# reference_nrf52840_module.net
KiCad netlist of a schematic drawn in EAGLE
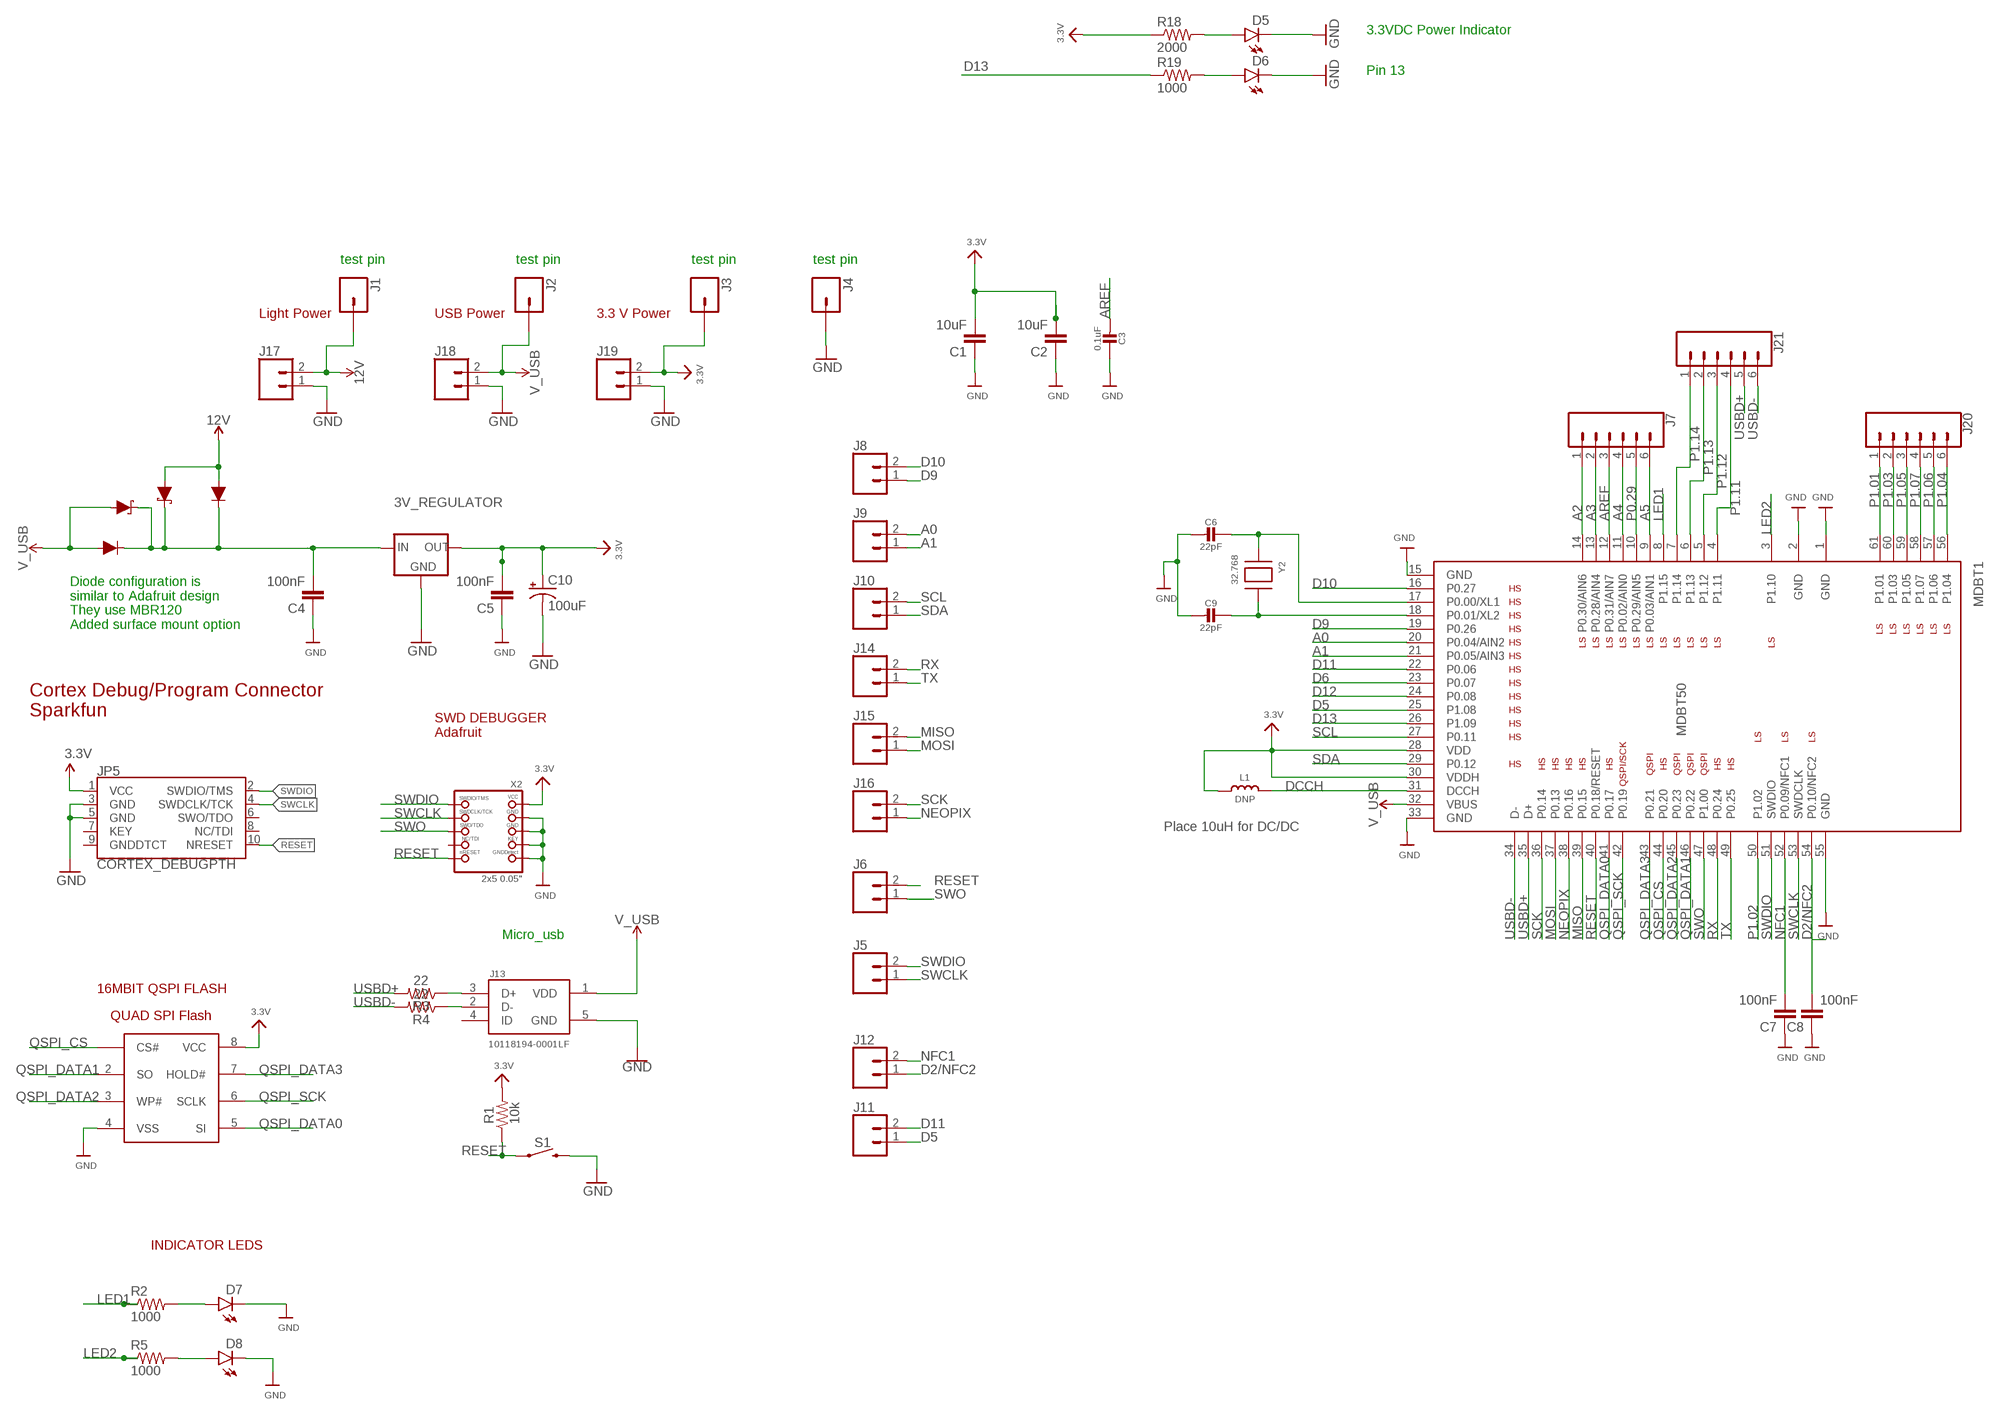
[diagram p0: schematic, sheet 1]

(export (version "E")
  (design (tool "Eeschema 10.0.6"))
  (components
    (comp (ref "3V_REGULATOR")
      (value "LDL1117_5V_REG")
      (footprint "eagle-import:SOT223")
      (libsource (lib "eagle-import") (part "LDL1117_5V_REG"))
    )
    (comp (ref "C1")
      (value "10uF")
      (footprint "eagle-import:0805")
      (libsource (lib "eagle-import") (part "10UF-0805-10V-10%"))
    )
    (comp (ref "C2")
      (value "10uF")
      (footprint "eagle-import:0805")
      (libsource (lib "eagle-import") (part "10UF-0805-10V-10%"))
    )
    (comp (ref "C3")
      (value "0.1uF")
      (footprint "eagle-import:_0805")
      (libsource (lib "eagle-import") (part "CAP_CERAMIC_0805"))
    )
    (comp (ref "C4")
      (value "100nF")
      (footprint "eagle-import:0805")
      (libsource (lib "eagle-import") (part "10UF-0805-10V-10%"))
    )
    (comp (ref "C5")
      (value "100nF")
      (footprint "eagle-import:0805")
      (libsource (lib "eagle-import") (part "10UF-0805-10V-10%"))
    )
    (comp (ref "C6")
      (value "22pF")
      (footprint "eagle-import:0603-NO")
      (libsource (lib "eagle-import") (part "CAP_CERAMIC0603_NO"))
    )
    (comp (ref "C7")
      (value "100nF")
      (footprint "eagle-import:0805")
      (libsource (lib "eagle-import") (part "10UF-0805-10V-10%"))
    )
    (comp (ref "C8")
      (value "100nF")
      (footprint "eagle-import:0805")
      (libsource (lib "eagle-import") (part "10UF-0805-10V-10%"))
    )
    (comp (ref "C9")
      (value "22pF")
      (footprint "eagle-import:0603-NO")
      (libsource (lib "eagle-import") (part "CAP_CERAMIC0603_NO"))
    )
    (comp (ref "C10")
      (value "100uF")
      (footprint "eagle-import:CPOL-RADIAL-2.5MM-6.5MM")
      (libsource (lib "eagle-import") (part "100UF-POLAR-RADIAL-2.5MM-25V-20%"))
    )
    (comp (ref "D1")
      (value "1A/50V/1.1V")
      (footprint "eagle-import:DIODE-1N4001")
      (libsource (lib "eagle-import") (part "DIODE-PTH"))
    )
    (comp (ref "D2")
      (value "1A/50V/1.1V")
      (footprint "eagle-import:DIODE-1N4001")
      (libsource (lib "eagle-import") (part "DIODE-PTH"))
    )
    (comp (ref "D3")
      (value "3A/40V/500mV")
      (footprint "eagle-import:SMA-DIODE")
      (libsource (lib "eagle-import") (part "DIODE-SCHOTTKY-B340A"))
    )
    (comp (ref "D4")
      (value "3A/40V/500mV")
      (footprint "eagle-import:SMA-DIODE")
      (libsource (lib "eagle-import") (part "DIODE-SCHOTTKY-B340A"))
    )
    (comp (ref "D5")
      (value "LED1206")
      (footprint "eagle-import:LED-1206")
      (libsource (lib "eagle-import") (part "LED1206"))
    )
    (comp (ref "D6")
      (value "LED1206")
      (footprint "eagle-import:LED-1206")
      (libsource (lib "eagle-import") (part "LED1206"))
    )
    (comp (ref "D7")
      (value "LED1206")
      (footprint "eagle-import:LED-1206")
      (libsource (lib "eagle-import") (part "LED1206"))
    )
    (comp (ref "D8")
      (value "LED1206")
      (footprint "eagle-import:LED-1206")
      (libsource (lib "eagle-import") (part "LED1206"))
    )
    (comp (ref "J1")
      (value "M01PTH")
      (footprint "eagle-import:1X01")
      (libsource (lib "eagle-import") (part "M01PTH"))
    )
    (comp (ref "J2")
      (value "M01PTH")
      (footprint "eagle-import:1X01")
      (libsource (lib "eagle-import") (part "M01PTH"))
    )
    (comp (ref "J3")
      (value "M01PTH")
      (footprint "eagle-import:1X01")
      (libsource (lib "eagle-import") (part "M01PTH"))
    )
    (comp (ref "J4")
      (value "M01PTH")
      (footprint "eagle-import:1X01")
      (libsource (lib "eagle-import") (part "M01PTH"))
    )
    (comp (ref "J5")
      (value "CONN_025MM")
      (footprint "eagle-import:SCREWTERMINAL-5MM-2")
      (libsource (lib "eagle-import") (part "CONN_025MM"))
    )
    (comp (ref "J6")
      (value "CONN_025MM")
      (footprint "eagle-import:SCREWTERMINAL-5MM-2")
      (libsource (lib "eagle-import") (part "CONN_025MM"))
    )
    (comp (ref "J7")
      (value "CONN_06NO_SILK_FEMALE_PTH")
      (footprint "eagle-import:1X06_NO_SILK")
      (libsource (lib "eagle-import") (part "CONN_06NO_SILK_FEMALE_PTH"))
    )
    (comp (ref "J8")
      (value "CONN_025MM")
      (footprint "eagle-import:SCREWTERMINAL-5MM-2")
      (libsource (lib "eagle-import") (part "CONN_025MM"))
    )
    (comp (ref "J9")
      (value "CONN_025MM")
      (footprint "eagle-import:SCREWTERMINAL-5MM-2")
      (libsource (lib "eagle-import") (part "CONN_025MM"))
    )
    (comp (ref "J10")
      (value "CONN_025MM")
      (footprint "eagle-import:SCREWTERMINAL-5MM-2")
      (libsource (lib "eagle-import") (part "CONN_025MM"))
    )
    (comp (ref "J11")
      (value "CONN_025MM")
      (footprint "eagle-import:SCREWTERMINAL-5MM-2")
      (libsource (lib "eagle-import") (part "CONN_025MM"))
    )
    (comp (ref "J12")
      (value "CONN_025MM")
      (footprint "eagle-import:SCREWTERMINAL-5MM-2")
      (libsource (lib "eagle-import") (part "CONN_025MM"))
    )
    (comp (ref "J13")
      (value "10118194-0001LF")
      (footprint "eagle-import:FRAMATOME_10118194-0001LF")
      (fields (field (name "MF") "Amphenol ICC"))
      (libsource (lib "eagle-import") (part "10118194-0001LF"))
    )
    (comp (ref "J14")
      (value "CONN_025MM")
      (footprint "eagle-import:SCREWTERMINAL-5MM-2")
      (libsource (lib "eagle-import") (part "CONN_025MM"))
    )
    (comp (ref "J15")
      (value "CONN_025MM")
      (footprint "eagle-import:SCREWTERMINAL-5MM-2")
      (libsource (lib "eagle-import") (part "CONN_025MM"))
    )
    (comp (ref "J16")
      (value "CONN_025MM")
      (footprint "eagle-import:SCREWTERMINAL-5MM-2")
      (libsource (lib "eagle-import") (part "CONN_025MM"))
    )
    (comp (ref "J17")
      (value "CONN_025MM")
      (footprint "eagle-import:SCREWTERMINAL-5MM-2")
      (libsource (lib "eagle-import") (part "CONN_025MM"))
    )
    (comp (ref "J18")
      (value "CONN_025MM")
      (footprint "eagle-import:SCREWTERMINAL-5MM-2")
      (libsource (lib "eagle-import") (part "CONN_025MM"))
    )
    (comp (ref "J19")
      (value "CONN_025MM")
      (footprint "eagle-import:SCREWTERMINAL-5MM-2")
      (libsource (lib "eagle-import") (part "CONN_025MM"))
    )
    (comp (ref "J20")
      (value "CONN_06NO_SILK_FEMALE_PTH")
      (footprint "eagle-import:1X06_NO_SILK")
      (libsource (lib "eagle-import") (part "CONN_06NO_SILK_FEMALE_PTH"))
    )
    (comp (ref "J21")
      (value "CONN_06NO_SILK_FEMALE_PTH")
      (footprint "eagle-import:1X06_NO_SILK")
      (libsource (lib "eagle-import") (part "CONN_06NO_SILK_FEMALE_PTH"))
    )
    (comp (ref "JP5")
      (value "CORTEX_DEBUGPTH")
      (footprint "eagle-import:2X5-PTH-1.27MM")
      (libsource (lib "eagle-import") (part "CORTEX_DEBUGPTH"))
    )
    (comp (ref "L1")
      (value "DNP")
      (footprint "eagle-import:_0805MP")
      (libsource (lib "eagle-import") (part "INDUCTOR_0805MP"))
    )
    (comp (ref "MDBT1")
      (value "MDBT50")
      (footprint "eagle-import:MDBT50")
      (libsource (lib "eagle-import") (part "MDBT50"))
    )
    (comp (ref "R1")
      (value "10k")
      (footprint "eagle-import:0805")
      (libsource (lib "eagle-import") (part "RESISTOR0805"))
    )
    (comp (ref "R2")
      (value "1000")
      (footprint "eagle-import:0805")
      (libsource (lib "eagle-import") (part "RESISTOR0805-RES"))
    )
    (comp (ref "R3")
      (value "22")
      (footprint "eagle-import:0805")
      (libsource (lib "eagle-import") (part "RESISTOR0805"))
    )
    (comp (ref "R4")
      (value "22")
      (footprint "eagle-import:0805")
      (libsource (lib "eagle-import") (part "RESISTOR0805"))
    )
    (comp (ref "R5")
      (value "1000")
      (footprint "eagle-import:0805")
      (libsource (lib "eagle-import") (part "RESISTOR0805-RES"))
    )
    (comp (ref "R18")
      (value "2000")
      (footprint "eagle-import:0805")
      (libsource (lib "eagle-import") (part "RESISTOR0805-RES"))
    )
    (comp (ref "R19")
      (value "1000")
      (footprint "eagle-import:0805")
      (libsource (lib "eagle-import") (part "RESISTOR0805-RES"))
    )
    (comp (ref "S1")
      (value "MOMENTARY-SWITCH-SPST-PTH-6.0MM-KIT")
      (footprint "eagle-import:TACTILE_SWITCH_PTH_6.0MM_KIT")
      (libsource (lib "eagle-import") (part "MOMENTARY-SWITCH-SPST-PTH-6.0MM-KIT"))
    )
    (comp (ref "U$4")
      (value "QUAD_SPI_FLASH")
      (footprint "eagle-import:SO08")
      (libsource (lib "eagle-import") (part "QUAD_SPI_FLASH"))
    )
    (comp (ref "X2")
      (value "2x5 0.05\"")
      (footprint "eagle-import:2X05_1.27MM_BOX_POSTS")
      (libsource (lib "eagle-import") (part "JTAG-CORTEXBOXPOSTS"))
    )
    (comp (ref "Y2")
      (value "32.768")
      (footprint "eagle-import:XTAL3215")
      (libsource (lib "eagle-import") (part "XTAL-3.2X1.5"))
    )
  )
  (nets
    (net (code "1") (name "/A0") (class "Default")
      (node (ref "J9") (pin "2") (pinfunction "2_2") (pintype "passive"))
      (node (ref "MDBT1") (pin "20") (pinfunction "P0.04/AIN2_20") (pintype "bidirectional"))
    )
    (net (code "2") (name "/A1") (class "Default")
      (node (ref "J9") (pin "1") (pinfunction "1_1") (pintype "passive"))
      (node (ref "MDBT1") (pin "21") (pinfunction "P0.05/AIN3_21") (pintype "bidirectional"))
    )
    (net (code "3") (name "/A2") (class "Default")
      (node (ref "J7") (pin "1") (pinfunction "1_1") (pintype "passive"))
      (node (ref "MDBT1") (pin "14") (pinfunction "P0.30/AIN6_14") (pintype "bidirectional"))
    )
    (net (code "4") (name "/A3") (class "Default")
      (node (ref "J7") (pin "2") (pinfunction "2_2") (pintype "passive"))
      (node (ref "MDBT1") (pin "13") (pinfunction "P0.28/AIN4_13") (pintype "bidirectional"))
    )
    (net (code "5") (name "/A4") (class "Default")
      (node (ref "J7") (pin "4") (pinfunction "4_4") (pintype "passive"))
      (node (ref "MDBT1") (pin "11") (pinfunction "P0.02/AIN0_11") (pintype "bidirectional"))
    )
    (net (code "6") (name "/A5") (class "Default")
      (node (ref "J7") (pin "6") (pinfunction "6_6") (pintype "passive"))
      (node (ref "MDBT1") (pin "9") (pinfunction "P0.03/AIN1_9") (pintype "bidirectional"))
    )
    (net (code "7") (name "/AREF") (class "Default")
      (node (ref "C3") (pin "2") (pinfunction "2_2") (pintype "passive"))
      (node (ref "J7") (pin "3") (pinfunction "3_3") (pintype "passive"))
      (node (ref "MDBT1") (pin "12") (pinfunction "P0.31/AIN7_12") (pintype "bidirectional"))
    )
    (net (code "8") (name "/D2{slash}NFC2") (class "Default")
      (node (ref "C8") (pin "2") (pinfunction "2_2") (pintype "passive"))
      (node (ref "J12") (pin "1") (pinfunction "1_1") (pintype "passive"))
      (node (ref "MDBT1") (pin "54") (pinfunction "P0.10/NFC2_54") (pintype "bidirectional"))
    )
    (net (code "9") (name "/D5") (class "Default")
      (node (ref "J11") (pin "1") (pinfunction "1_1") (pintype "passive"))
      (node (ref "MDBT1") (pin "25") (pinfunction "P1.08_25") (pintype "bidirectional"))
    )
    (net (code "10") (name "/D6") (class "Default")
      (node (ref "MDBT1") (pin "23") (pinfunction "P0.07_23") (pintype "bidirectional"))
    )
    (net (code "11") (name "/D9") (class "Default")
      (node (ref "J8") (pin "1") (pinfunction "1_1") (pintype "passive"))
      (node (ref "MDBT1") (pin "19") (pinfunction "P0.26_19") (pintype "bidirectional"))
    )
    (net (code "12") (name "/D10") (class "Default")
      (node (ref "J8") (pin "2") (pinfunction "2_2") (pintype "passive"))
      (node (ref "MDBT1") (pin "16") (pinfunction "P0.27_16") (pintype "bidirectional"))
    )
    (net (code "13") (name "/D11") (class "Default")
      (node (ref "J11") (pin "2") (pinfunction "2_2") (pintype "passive"))
      (node (ref "MDBT1") (pin "22") (pinfunction "P0.06_22") (pintype "bidirectional"))
    )
    (net (code "14") (name "/D12") (class "Default")
      (node (ref "MDBT1") (pin "24") (pinfunction "P0.08_24") (pintype "bidirectional"))
    )
    (net (code "15") (name "/D13") (class "Default")
      (node (ref "MDBT1") (pin "26") (pinfunction "P1.09_26") (pintype "bidirectional"))
      (node (ref "R19") (pin "1") (pinfunction "1_1") (pintype "passive"))
    )
    (net (code "16") (name "/DCCH") (class "Default")
      (node (ref "L1") (pin "2") (pinfunction "2_2") (pintype "passive"))
      (node (ref "MDBT1") (pin "31") (pinfunction "DCCH_31") (pintype "bidirectional"))
    )
    (net (code "17") (name "/LED1") (class "Default")
      (node (ref "MDBT1") (pin "8") (pinfunction "P1.15_8") (pintype "bidirectional"))
      (node (ref "R2") (pin "1") (pinfunction "1_1") (pintype "passive"))
    )
    (net (code "18") (name "/LED2") (class "Default")
      (node (ref "MDBT1") (pin "3") (pinfunction "P1.10_3") (pintype "bidirectional"))
      (node (ref "R5") (pin "1") (pinfunction "1_1") (pintype "passive"))
    )
    (net (code "19") (name "/MISO") (class "Default")
      (node (ref "J15") (pin "2") (pinfunction "2_2") (pintype "passive"))
      (node (ref "MDBT1") (pin "39") (pinfunction "P0.15_39") (pintype "bidirectional"))
    )
    (net (code "20") (name "/MOSI") (class "Default")
      (node (ref "J15") (pin "1") (pinfunction "1_1") (pintype "passive"))
      (node (ref "MDBT1") (pin "37") (pinfunction "P0.13_37") (pintype "bidirectional"))
    )
    (net (code "21") (name "/NEOPIX") (class "Default")
      (node (ref "J16") (pin "1") (pinfunction "1_1") (pintype "passive"))
      (node (ref "MDBT1") (pin "38") (pinfunction "P0.16_38") (pintype "bidirectional"))
    )
    (net (code "22") (name "/NFC1") (class "Default")
      (node (ref "C7") (pin "2") (pinfunction "2_2") (pintype "passive"))
      (node (ref "J12") (pin "2") (pinfunction "2_2") (pintype "passive"))
      (node (ref "MDBT1") (pin "52") (pinfunction "P0.09/NFC1_52") (pintype "bidirectional"))
    )
    (net (code "23") (name "/P0.29") (class "Default")
      (node (ref "J7") (pin "5") (pinfunction "5_5") (pintype "passive"))
      (node (ref "MDBT1") (pin "10") (pinfunction "P0.29/AIN5_10") (pintype "bidirectional"))
    )
    (net (code "24") (name "/P1.01") (class "Default")
      (node (ref "J20") (pin "1") (pinfunction "1_1") (pintype "passive"))
      (node (ref "MDBT1") (pin "61") (pinfunction "P1.01_61") (pintype "bidirectional"))
    )
    (net (code "25") (name "/P1.02") (class "Default")
      (node (ref "MDBT1") (pin "50") (pinfunction "P1.02_50") (pintype "bidirectional"))
    )
    (net (code "26") (name "/P1.03") (class "Default")
      (node (ref "J20") (pin "2") (pinfunction "2_2") (pintype "passive"))
      (node (ref "MDBT1") (pin "60") (pinfunction "P1.03_60") (pintype "bidirectional"))
    )
    (net (code "27") (name "/P1.04") (class "Default")
      (node (ref "J20") (pin "6") (pinfunction "6_6") (pintype "passive"))
      (node (ref "MDBT1") (pin "56") (pinfunction "P1.04_56") (pintype "bidirectional"))
    )
    (net (code "28") (name "/P1.05") (class "Default")
      (node (ref "J20") (pin "3") (pinfunction "3_3") (pintype "passive"))
      (node (ref "MDBT1") (pin "59") (pinfunction "P1.05_59") (pintype "bidirectional"))
    )
    (net (code "29") (name "/P1.06") (class "Default")
      (node (ref "J20") (pin "5") (pinfunction "5_5") (pintype "passive"))
      (node (ref "MDBT1") (pin "57") (pinfunction "P1.06_57") (pintype "bidirectional"))
    )
    (net (code "30") (name "/P1.07") (class "Default")
      (node (ref "J20") (pin "4") (pinfunction "4_4") (pintype "passive"))
      (node (ref "MDBT1") (pin "58") (pinfunction "P1.07_58") (pintype "bidirectional"))
    )
    (net (code "31") (name "/P1.11") (class "Default")
      (node (ref "J21") (pin "4") (pinfunction "4_4") (pintype "passive"))
      (node (ref "MDBT1") (pin "4") (pinfunction "P1.11_4") (pintype "bidirectional"))
    )
    (net (code "32") (name "/P1.12") (class "Default")
      (node (ref "J21") (pin "3") (pinfunction "3_3") (pintype "passive"))
      (node (ref "MDBT1") (pin "5") (pinfunction "P1.12_5") (pintype "bidirectional"))
    )
    (net (code "33") (name "/P1.13") (class "Default")
      (node (ref "J21") (pin "2") (pinfunction "2_2") (pintype "passive"))
      (node (ref "MDBT1") (pin "6") (pinfunction "P1.13_6") (pintype "bidirectional"))
    )
    (net (code "34") (name "/P1.14") (class "Default")
      (node (ref "J21") (pin "1") (pinfunction "1_1") (pintype "passive"))
      (node (ref "MDBT1") (pin "7") (pinfunction "P1.14_7") (pintype "bidirectional"))
    )
    (net (code "35") (name "/QSPI_CS") (class "Default")
      (node (ref "MDBT1") (pin "44") (pinfunction "P0.20_44") (pintype "bidirectional"))
      (node (ref "U$4") (pin "1") (pinfunction "CS#_1") (pintype "bidirectional"))
    )
    (net (code "36") (name "/QSPI_DATA0") (class "Default")
      (node (ref "MDBT1") (pin "41") (pinfunction "P0.17_41") (pintype "bidirectional"))
      (node (ref "U$4") (pin "5") (pinfunction "SI_5") (pintype "bidirectional"))
    )
    (net (code "37") (name "/QSPI_DATA1") (class "Default")
      (node (ref "MDBT1") (pin "46") (pinfunction "P0.22_46") (pintype "bidirectional"))
      (node (ref "U$4") (pin "2") (pinfunction "SO_2") (pintype "bidirectional"))
    )
    (net (code "38") (name "/QSPI_DATA2") (class "Default")
      (node (ref "MDBT1") (pin "45") (pinfunction "P0.23_45") (pintype "bidirectional"))
      (node (ref "U$4") (pin "3") (pinfunction "WP#_3") (pintype "bidirectional"))
    )
    (net (code "39") (name "/QSPI_DATA3") (class "Default")
      (node (ref "MDBT1") (pin "43") (pinfunction "P0.21_43") (pintype "bidirectional"))
      (node (ref "U$4") (pin "7") (pinfunction "HOLD#_7") (pintype "bidirectional"))
    )
    (net (code "40") (name "/QSPI_SCK") (class "Default")
      (node (ref "MDBT1") (pin "42") (pinfunction "P0.19_42") (pintype "bidirectional"))
      (node (ref "U$4") (pin "6") (pinfunction "SCLK_6") (pintype "bidirectional"))
    )
    (net (code "41") (name "/RX") (class "Default")
      (node (ref "J14") (pin "2") (pinfunction "2_2") (pintype "passive"))
      (node (ref "MDBT1") (pin "48") (pinfunction "P0.24_48") (pintype "bidirectional"))
    )
    (net (code "42") (name "/SCK") (class "Default")
      (node (ref "J16") (pin "2") (pinfunction "2_2") (pintype "passive"))
      (node (ref "MDBT1") (pin "36") (pinfunction "P0.14_36") (pintype "bidirectional"))
    )
    (net (code "43") (name "/SCL") (class "Default")
      (node (ref "J10") (pin "2") (pinfunction "2_2") (pintype "passive"))
      (node (ref "MDBT1") (pin "27") (pinfunction "P0.11_27") (pintype "bidirectional"))
    )
    (net (code "44") (name "/SDA") (class "Default")
      (node (ref "J10") (pin "1") (pinfunction "1_1") (pintype "passive"))
      (node (ref "MDBT1") (pin "29") (pinfunction "P0.12_29") (pintype "bidirectional"))
    )
    (net (code "45") (name "/SWO") (class "Default")
      (node (ref "J6") (pin "1") (pinfunction "1_1") (pintype "passive"))
      (node (ref "MDBT1") (pin "47") (pinfunction "P1.00_47") (pintype "bidirectional"))
      (node (ref "X2") (pin "6") (pinfunction "SWO_6") (pintype "bidirectional"))
    )
    (net (code "46") (name "/TX") (class "Default")
      (node (ref "J14") (pin "1") (pinfunction "1_1") (pintype "passive"))
      (node (ref "MDBT1") (pin "49") (pinfunction "P0.25_49") (pintype "bidirectional"))
    )
    (net (code "47") (name "/USBD+") (class "Default")
      (node (ref "J21") (pin "5") (pinfunction "5_5") (pintype "passive"))
      (node (ref "MDBT1") (pin "35") (pinfunction "D+_35") (pintype "bidirectional"))
      (node (ref "R3") (pin "2") (pinfunction "2_2") (pintype "passive"))
    )
    (net (code "48") (name "/USBD-") (class "Default")
      (node (ref "J21") (pin "6") (pinfunction "6_6") (pintype "passive"))
      (node (ref "MDBT1") (pin "34") (pinfunction "D-_34") (pintype "bidirectional"))
      (node (ref "R4") (pin "2") (pinfunction "2_2") (pintype "passive"))
    )
    (net (code "49") (name "3.3V") (class "Default")
      (node (ref "3V_REGULATOR") (pin "2") (pinfunction "OUT_2") (pintype "passive"))
      (node (ref "3V_REGULATOR") (pin "4") (pinfunction "OUT_4") (pintype "passive"))
      (node (ref "C1") (pin "2") (pinfunction "2_2") (pintype "passive"))
      (node (ref "C10") (pin "1") (pinfunction "+_1") (pintype "passive"))
      (node (ref "C2") (pin "2") (pinfunction "2_2") (pintype "passive"))
      (node (ref "C5") (pin "2") (pinfunction "2_2") (pintype "passive"))
      (node (ref "J19") (pin "2") (pinfunction "2_2") (pintype "passive"))
      (node (ref "J3") (pin "1") (pinfunction "1_1") (pintype "passive"))
      (node (ref "JP5") (pin "1") (pinfunction "VCC_1") (pintype "bidirectional"))
      (node (ref "L1") (pin "1") (pinfunction "1_1") (pintype "passive"))
      (node (ref "MDBT1") (pin "28") (pinfunction "VDD_28") (pintype "bidirectional"))
      (node (ref "MDBT1") (pin "30") (pinfunction "VDDH_30") (pintype "bidirectional"))
      (node (ref "R1") (pin "2") (pinfunction "2_2") (pintype "passive"))
      (node (ref "R18") (pin "1") (pinfunction "1_1") (pintype "passive"))
      (node (ref "U$4") (pin "8") (pinfunction "VCC_8") (pintype "bidirectional"))
      (node (ref "X2") (pin "1") (pinfunction "VCC_1") (pintype "power_in"))
    )
    (net (code "50") (name "12V") (class "Default")
      (node (ref "D1") (pin "A") (pinfunction "A_A") (pintype "passive"))
      (node (ref "D3") (pin "A") (pinfunction "A_A") (pintype "passive"))
      (node (ref "J1") (pin "1") (pinfunction "1_1") (pintype "passive"))
      (node (ref "J17") (pin "2") (pinfunction "2_2") (pintype "passive"))
    )
    (net (code "51") (name "GND") (class "Default")
      (node (ref "3V_REGULATOR") (pin "1") (pinfunction "GND_1") (pintype "input"))
      (node (ref "C1") (pin "1") (pinfunction "1_1") (pintype "passive"))
      (node (ref "C10") (pin "2") (pinfunction "-_2") (pintype "passive"))
      (node (ref "C2") (pin "1") (pinfunction "1_1") (pintype "passive"))
      (node (ref "C3") (pin "1") (pinfunction "1_1") (pintype "passive"))
      (node (ref "C4") (pin "1") (pinfunction "1_1") (pintype "passive"))
      (node (ref "C5") (pin "1") (pinfunction "1_1") (pintype "passive"))
      (node (ref "C6") (pin "2") (pinfunction "2_2") (pintype "passive"))
      (node (ref "C7") (pin "1") (pinfunction "1_1") (pintype "passive"))
      (node (ref "C8") (pin "1") (pinfunction "1_1") (pintype "passive"))
      (node (ref "C9") (pin "2") (pinfunction "2_2") (pintype "passive"))
      (node (ref "D5") (pin "C") (pinfunction "C_C") (pintype "passive"))
      (node (ref "D6") (pin "C") (pinfunction "C_C") (pintype "passive"))
      (node (ref "D7") (pin "C") (pinfunction "C_C") (pintype "passive"))
      (node (ref "D8") (pin "C") (pinfunction "C_C") (pintype "passive"))
      (node (ref "J13") (pin "5") (pinfunction "GND_5") (pintype "power_in"))
      (node (ref "J17") (pin "1") (pinfunction "1_1") (pintype "passive"))
      (node (ref "J18") (pin "1") (pinfunction "1_1") (pintype "passive"))
      (node (ref "J19") (pin "1") (pinfunction "1_1") (pintype "passive"))
      (node (ref "J4") (pin "1") (pinfunction "1_1") (pintype "passive"))
      (node (ref "JP5") (pin "3") (pinfunction "GND_3") (pintype "bidirectional"))
      (node (ref "JP5") (pin "5") (pinfunction "GND_5") (pintype "bidirectional"))
      (node (ref "MDBT1") (pin "1") (pinfunction "GND_1") (pintype "bidirectional"))
      (node (ref "MDBT1") (pin "15") (pinfunction "GND_15") (pintype "bidirectional"))
      (node (ref "MDBT1") (pin "2") (pinfunction "GND_2") (pintype "bidirectional"))
      (node (ref "MDBT1") (pin "33") (pinfunction "GND_33") (pintype "bidirectional"))
      (node (ref "MDBT1") (pin "55") (pinfunction "GND_55") (pintype "bidirectional"))
      (node (ref "S1") (pin "3") (pinfunction "2_3") (pintype "passive"))
      (node (ref "U$4") (pin "4") (pinfunction "VSS_4") (pintype "bidirectional"))
      (node (ref "X2") (pin "3") (pinfunction "GND_3") (pintype "power_in"))
      (node (ref "X2") (pin "5") (pinfunction "GND_5") (pintype "power_in"))
      (node (ref "X2") (pin "7") (pinfunction "KEY_7") (pintype "bidirectional"))
      (node (ref "X2") (pin "9") (pinfunction "GNDDETECT_9") (pintype "bidirectional"))
    )
    (net (code "52") (name "Net-(3V_REGULATOR-IN)") (class "Default")
      (node (ref "3V_REGULATOR") (pin "3") (pinfunction "IN_3") (pintype "input"))
      (node (ref "C4") (pin "2") (pinfunction "2_2") (pintype "passive"))
      (node (ref "D1") (pin "C") (pinfunction "C_C") (pintype "passive"))
      (node (ref "D2") (pin "C") (pinfunction "C_C") (pintype "passive"))
      (node (ref "D3") (pin "C") (pinfunction "C_C") (pintype "passive"))
      (node (ref "D4") (pin "C") (pinfunction "C_C") (pintype "passive"))
    )
    (net (code "53") (name "Net-(D5-PadA)") (class "Default")
      (node (ref "D5") (pin "A") (pinfunction "A_A") (pintype "passive"))
      (node (ref "R18") (pin "2") (pinfunction "2_2") (pintype "passive"))
    )
    (net (code "54") (name "Net-(D6-PadA)") (class "Default")
      (node (ref "D6") (pin "A") (pinfunction "A_A") (pintype "passive"))
      (node (ref "R19") (pin "2") (pinfunction "2_2") (pintype "passive"))
    )
    (net (code "55") (name "Net-(D7-PadA)") (class "Default")
      (node (ref "D7") (pin "A") (pinfunction "A_A") (pintype "passive"))
      (node (ref "R2") (pin "2") (pinfunction "2_2") (pintype "passive"))
    )
    (net (code "56") (name "Net-(D8-PadA)") (class "Default")
      (node (ref "D8") (pin "A") (pinfunction "A_A") (pintype "passive"))
      (node (ref "R5") (pin "2") (pinfunction "2_2") (pintype "passive"))
    )
    (net (code "57") (name "Net-(J13-D+)") (class "Default")
      (node (ref "J13") (pin "3") (pinfunction "D+_3") (pintype "bidirectional"))
      (node (ref "R3") (pin "1") (pinfunction "1_1") (pintype "passive"))
    )
    (net (code "58") (name "Net-(J13-D-)") (class "Default")
      (node (ref "J13") (pin "2") (pinfunction "D-_2") (pintype "bidirectional"))
      (node (ref "R4") (pin "1") (pinfunction "1_1") (pintype "passive"))
    )
    (net (code "59") (name "Net-(MDBT1-P0.00{slash}XL1)") (class "Default")
      (node (ref "C6") (pin "1") (pinfunction "1_1") (pintype "passive"))
      (node (ref "MDBT1") (pin "17") (pinfunction "P0.00/XL1_17") (pintype "bidirectional"))
      (node (ref "Y2") (pin "P$1") (pinfunction "P$1_P$1") (pintype "bidirectional"))
    )
    (net (code "60") (name "Net-(MDBT1-P0.01{slash}XL2)") (class "Default")
      (node (ref "C9") (pin "1") (pinfunction "1_1") (pintype "passive"))
      (node (ref "MDBT1") (pin "18") (pinfunction "P0.01/XL2_18") (pintype "bidirectional"))
      (node (ref "Y2") (pin "P$2") (pinfunction "P$2_P$2") (pintype "bidirectional"))
    )
    (net (code "61") (name "RESET") (class "Default")
      (node (ref "J6") (pin "2") (pinfunction "2_2") (pintype "passive"))
      (node (ref "JP5") (pin "10") (pinfunction "NRESET_10") (pintype "bidirectional"))
      (node (ref "MDBT1") (pin "40") (pinfunction "P0.18/RESET_40") (pintype "bidirectional"))
      (node (ref "R1") (pin "1") (pinfunction "1_1") (pintype "passive"))
      (node (ref "S1") (pin "1") (pinfunction "1_1") (pintype "passive"))
      (node (ref "X2") (pin "10") (pinfunction "NRESET_10") (pintype "bidirectional"))
    )
    (net (code "62") (name "SWCLK") (class "Default")
      (node (ref "J5") (pin "1") (pinfunction "1_1") (pintype "passive"))
      (node (ref "JP5") (pin "4") (pinfunction "SWDCLK/TCK_4") (pintype "bidirectional"))
      (node (ref "MDBT1") (pin "53") (pinfunction "SWDCLK_53") (pintype "bidirectional"))
      (node (ref "X2") (pin "4") (pinfunction "SWDCLK_4") (pintype "bidirectional"))
    )
    (net (code "63") (name "SWDIO") (class "Default")
      (node (ref "J5") (pin "2") (pinfunction "2_2") (pintype "passive"))
      (node (ref "JP5") (pin "2") (pinfunction "SWDIO/TMS_2") (pintype "bidirectional"))
      (node (ref "MDBT1") (pin "51") (pinfunction "SWDIO_51") (pintype "bidirectional"))
      (node (ref "X2") (pin "2") (pinfunction "SWDIO_2") (pintype "bidirectional"))
    )
    (net (code "64") (name "V_USB") (class "Default")
      (node (ref "D2") (pin "A") (pinfunction "A_A") (pintype "passive"))
      (node (ref "D4") (pin "A") (pinfunction "A_A") (pintype "passive"))
      (node (ref "J13") (pin "1") (pinfunction "VDD_1") (pintype "power_in"))
      (node (ref "J18") (pin "2") (pinfunction "2_2") (pintype "passive"))
      (node (ref "J2") (pin "1") (pinfunction "1_1") (pintype "passive"))
      (node (ref "MDBT1") (pin "32") (pinfunction "VBUS_32") (pintype "bidirectional"))
    )
    (net (code "65") (name "unconnected-(J13-ID-Pad4)") (class "Default")
      (node (ref "J13") (pin "4") (pinfunction "ID_4") (pintype "passive"))
    )
    (net (code "66") (name "unconnected-(JP5-GNDDTCT-Pad9)") (class "Default")
      (node (ref "JP5") (pin "9") (pinfunction "GNDDTCT_9") (pintype "bidirectional"))
    )
    (net (code "67") (name "unconnected-(JP5-KEY-Pad7)") (class "Default")
      (node (ref "JP5") (pin "7") (pinfunction "KEY_7") (pintype "bidirectional"))
    )
    (net (code "68") (name "unconnected-(JP5-NC{slash}TDI-Pad8)") (class "Default")
      (node (ref "JP5") (pin "8") (pinfunction "NC/TDI_8") (pintype "bidirectional"))
    )
    (net (code "69") (name "unconnected-(JP5-SWO{slash}TDO-Pad6)") (class "Default")
      (node (ref "JP5") (pin "6") (pinfunction "SWO/TDO_6") (pintype "bidirectional"))
    )
    (net (code "70") (name "unconnected-(X2-TDI-Pad8)") (class "Default")
      (node (ref "X2") (pin "8") (pinfunction "TDI_8") (pintype "bidirectional"))
    )
  )
)
